# Proppeler_Clock.net
KiCad netlist of a schematic drawn in EAGLE
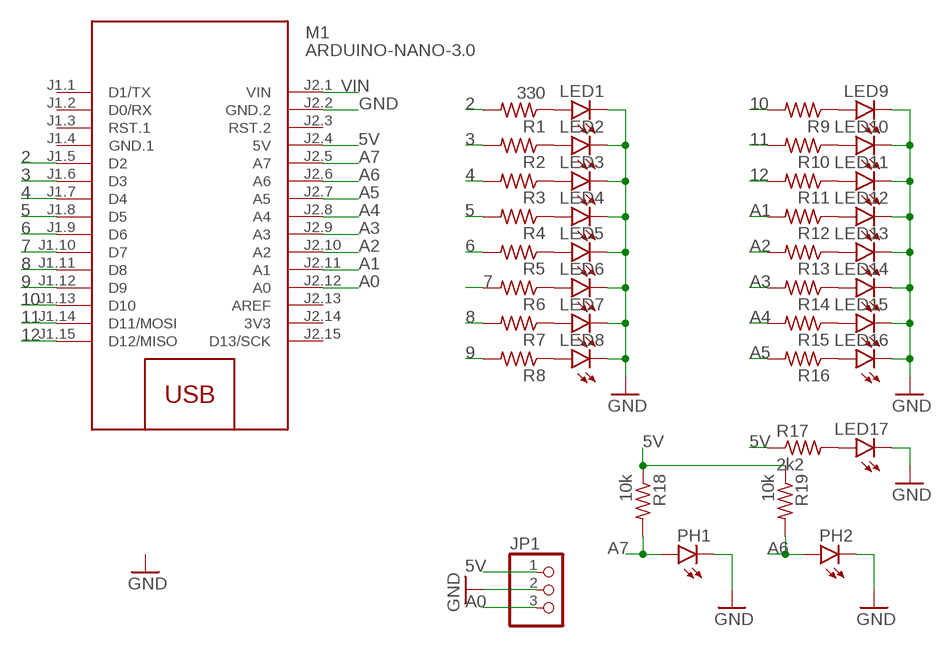
[diagram p0: schematic, sheet 1]

(export (version "E")
  (design (tool "Eeschema 10.0.6"))
  (components
    (comp (ref "JP1")
      (value "PINHD-1X3")
      (footprint "eagle-import:1X03")
      (libsource (lib "eagle-import") (part "PINHD-1X3"))
    )
    (comp (ref "LED1")
      (value "LED3MM")
      (footprint "eagle-import:LED3MM")
      (libsource (lib "eagle-import") (part "LED3MM"))
    )
    (comp (ref "LED2")
      (value "LED3MM")
      (footprint "eagle-import:LED3MM")
      (libsource (lib "eagle-import") (part "LED3MM"))
    )
    (comp (ref "LED3")
      (value "LED3MM")
      (footprint "eagle-import:LED3MM")
      (libsource (lib "eagle-import") (part "LED3MM"))
    )
    (comp (ref "LED4")
      (value "LED3MM")
      (footprint "eagle-import:LED3MM")
      (libsource (lib "eagle-import") (part "LED3MM"))
    )
    (comp (ref "LED5")
      (value "LED3MM")
      (footprint "eagle-import:LED3MM")
      (libsource (lib "eagle-import") (part "LED3MM"))
    )
    (comp (ref "LED6")
      (value "LED3MM")
      (footprint "eagle-import:LED3MM")
      (libsource (lib "eagle-import") (part "LED3MM"))
    )
    (comp (ref "LED7")
      (value "LED3MM")
      (footprint "eagle-import:LED3MM")
      (libsource (lib "eagle-import") (part "LED3MM"))
    )
    (comp (ref "LED8")
      (value "LED3MM")
      (footprint "eagle-import:LED3MM")
      (libsource (lib "eagle-import") (part "LED3MM"))
    )
    (comp (ref "LED9")
      (value "LED3MM")
      (footprint "eagle-import:LED3MM")
      (libsource (lib "eagle-import") (part "LED3MM"))
    )
    (comp (ref "LED10")
      (value "LED3MM")
      (footprint "eagle-import:LED3MM")
      (libsource (lib "eagle-import") (part "LED3MM"))
    )
    (comp (ref "LED11")
      (value "LED3MM")
      (footprint "eagle-import:LED3MM")
      (libsource (lib "eagle-import") (part "LED3MM"))
    )
    (comp (ref "LED12")
      (value "LED3MM")
      (footprint "eagle-import:LED3MM")
      (libsource (lib "eagle-import") (part "LED3MM"))
    )
    (comp (ref "LED13")
      (value "LED3MM")
      (footprint "eagle-import:LED3MM")
      (libsource (lib "eagle-import") (part "LED3MM"))
    )
    (comp (ref "LED14")
      (value "LED3MM")
      (footprint "eagle-import:LED3MM")
      (libsource (lib "eagle-import") (part "LED3MM"))
    )
    (comp (ref "LED15")
      (value "LED3MM")
      (footprint "eagle-import:LED3MM")
      (libsource (lib "eagle-import") (part "LED3MM"))
    )
    (comp (ref "LED16")
      (value "LED3MM")
      (footprint "eagle-import:LED3MM")
      (libsource (lib "eagle-import") (part "LED3MM"))
    )
    (comp (ref "LED17")
      (value "LED3MM")
      (footprint "eagle-import:LED3MM")
      (libsource (lib "eagle-import") (part "LED3MM"))
    )
    (comp (ref "M1")
      (value "ARDUINO-NANO-3.0")
      (footprint "eagle-import:ARDUINO-NANO-3.0")
      (libsource (lib "eagle-import") (part "ARDUINO-NANO-3.0"))
    )
    (comp (ref "PH1")
      (value "LED3MM")
      (footprint "eagle-import:LED3MM")
      (libsource (lib "eagle-import") (part "LED3MM"))
    )
    (comp (ref "PH2")
      (value "LED3MM")
      (footprint "eagle-import:LED3MM")
      (libsource (lib "eagle-import") (part "LED3MM"))
    )
    (comp (ref "R1")
      (value "330")
      (footprint "eagle-import:0204_7")
      (libsource (lib "eagle-import") (part "R-US_0204/7"))
    )
    (comp (ref "R2")
      (value "R-US_0204/7")
      (footprint "eagle-import:0204_7")
      (libsource (lib "eagle-import") (part "R-US_0204/7"))
    )
    (comp (ref "R3")
      (value "R-US_0204/7")
      (footprint "eagle-import:0204_7")
      (libsource (lib "eagle-import") (part "R-US_0204/7"))
    )
    (comp (ref "R4")
      (value "R-US_0204/7")
      (footprint "eagle-import:0204_7")
      (libsource (lib "eagle-import") (part "R-US_0204/7"))
    )
    (comp (ref "R5")
      (value "R-US_0204/7")
      (footprint "eagle-import:0204_7")
      (libsource (lib "eagle-import") (part "R-US_0204/7"))
    )
    (comp (ref "R6")
      (value "R-US_0204/7")
      (footprint "eagle-import:0204_7")
      (libsource (lib "eagle-import") (part "R-US_0204/7"))
    )
    (comp (ref "R7")
      (value "R-US_0204/7")
      (footprint "eagle-import:0204_7")
      (libsource (lib "eagle-import") (part "R-US_0204/7"))
    )
    (comp (ref "R8")
      (value "R-US_0204/7")
      (footprint "eagle-import:0204_7")
      (libsource (lib "eagle-import") (part "R-US_0204/7"))
    )
    (comp (ref "R9")
      (value "R-US_0204/7")
      (footprint "eagle-import:0204_7")
      (libsource (lib "eagle-import") (part "R-US_0204/7"))
    )
    (comp (ref "R10")
      (value "R-US_0204/7")
      (footprint "eagle-import:0204_7")
      (libsource (lib "eagle-import") (part "R-US_0204/7"))
    )
    (comp (ref "R11")
      (value "R-US_0204/7")
      (footprint "eagle-import:0204_7")
      (libsource (lib "eagle-import") (part "R-US_0204/7"))
    )
    (comp (ref "R12")
      (value "R-US_0204/7")
      (footprint "eagle-import:0204_7")
      (libsource (lib "eagle-import") (part "R-US_0204/7"))
    )
    (comp (ref "R13")
      (value "R-US_0204/7")
      (footprint "eagle-import:0204_7")
      (libsource (lib "eagle-import") (part "R-US_0204/7"))
    )
    (comp (ref "R14")
      (value "R-US_0204/7")
      (footprint "eagle-import:0204_7")
      (libsource (lib "eagle-import") (part "R-US_0204/7"))
    )
    (comp (ref "R15")
      (value "R-US_0204/7")
      (footprint "eagle-import:0204_7")
      (libsource (lib "eagle-import") (part "R-US_0204/7"))
    )
    (comp (ref "R16")
      (value "R-US_0204/7")
      (footprint "eagle-import:0204_7")
      (libsource (lib "eagle-import") (part "R-US_0204/7"))
    )
    (comp (ref "R17")
      (value "2k2")
      (footprint "eagle-import:0204_7")
      (libsource (lib "eagle-import") (part "R-US_0204/7"))
    )
    (comp (ref "R18")
      (value "10k")
      (footprint "eagle-import:0204_7")
      (libsource (lib "eagle-import") (part "R-US_0204/7"))
    )
    (comp (ref "R19")
      (value "10k")
      (footprint "eagle-import:0204_7")
      (libsource (lib "eagle-import") (part "R-US_0204/7"))
    )
  )
  (nets
    (net (code "1") (name "/2") (class "Default")
      (node (ref "M1") (pin "J1.5") (pinfunction "D2_J1.5") (pintype "bidirectional"))
      (node (ref "R1") (pin "2") (pinfunction "2_2") (pintype "passive"))
    )
    (net (code "2") (name "/3") (class "Default")
      (node (ref "M1") (pin "J1.6") (pinfunction "D3_J1.6") (pintype "bidirectional"))
      (node (ref "R2") (pin "2") (pinfunction "2_2") (pintype "passive"))
    )
    (net (code "3") (name "/3V3") (class "Default")
      (node (ref "M1") (pin "J2.14") (pinfunction "3V3_J2.14") (pintype "power_in"))
    )
    (net (code "4") (name "/4") (class "Default")
      (node (ref "M1") (pin "J1.7") (pinfunction "D4_J1.7") (pintype "bidirectional"))
      (node (ref "R3") (pin "2") (pinfunction "2_2") (pintype "passive"))
    )
    (net (code "5") (name "/5") (class "Default")
      (node (ref "M1") (pin "J1.8") (pinfunction "D5_J1.8") (pintype "bidirectional"))
      (node (ref "R4") (pin "2") (pinfunction "2_2") (pintype "passive"))
    )
    (net (code "6") (name "/5V") (class "Default")
      (node (ref "JP1") (pin "1") (pinfunction "1_1") (pintype "passive"))
      (node (ref "M1") (pin "J2.4") (pinfunction "5V_J2.4") (pintype "power_in"))
      (node (ref "R17") (pin "1") (pinfunction "1_1") (pintype "passive"))
      (node (ref "R18") (pin "1") (pinfunction "1_1") (pintype "passive"))
      (node (ref "R19") (pin "1") (pinfunction "1_1") (pintype "passive"))
    )
    (net (code "7") (name "/6") (class "Default")
      (node (ref "M1") (pin "J1.9") (pinfunction "D6_J1.9") (pintype "bidirectional"))
      (node (ref "R5") (pin "2") (pinfunction "2_2") (pintype "passive"))
    )
    (net (code "8") (name "/7") (class "Default")
      (node (ref "M1") (pin "J1.10") (pinfunction "D7_J1.10") (pintype "bidirectional"))
      (node (ref "R6") (pin "2") (pinfunction "2_2") (pintype "passive"))
    )
    (net (code "9") (name "/8") (class "Default")
      (node (ref "M1") (pin "J1.11") (pinfunction "D8_J1.11") (pintype "bidirectional"))
      (node (ref "R7") (pin "2") (pinfunction "2_2") (pintype "passive"))
    )
    (net (code "10") (name "/9") (class "Default")
      (node (ref "M1") (pin "J1.12") (pinfunction "D9_J1.12") (pintype "bidirectional"))
      (node (ref "R8") (pin "2") (pinfunction "2_2") (pintype "passive"))
    )
    (net (code "11") (name "/10") (class "Default")
      (node (ref "M1") (pin "J1.13") (pinfunction "D10_J1.13") (pintype "bidirectional"))
      (node (ref "R9") (pin "2") (pinfunction "2_2") (pintype "passive"))
    )
    (net (code "12") (name "/11") (class "Default")
      (node (ref "M1") (pin "J1.14") (pinfunction "D11/MOSI_J1.14") (pintype "bidirectional"))
      (node (ref "R10") (pin "2") (pinfunction "2_2") (pintype "passive"))
    )
    (net (code "13") (name "/12") (class "Default")
      (node (ref "M1") (pin "J1.15") (pinfunction "D12/MISO_J1.15") (pintype "bidirectional"))
      (node (ref "R11") (pin "2") (pinfunction "2_2") (pintype "passive"))
    )
    (net (code "14") (name "/A0") (class "Default")
      (node (ref "JP1") (pin "3") (pinfunction "3_3") (pintype "passive"))
      (node (ref "M1") (pin "J2.12") (pinfunction "A0_J2.12") (pintype "bidirectional"))
    )
    (net (code "15") (name "/A1") (class "Default")
      (node (ref "M1") (pin "J2.11") (pinfunction "A1_J2.11") (pintype "bidirectional"))
      (node (ref "R12") (pin "2") (pinfunction "2_2") (pintype "passive"))
    )
    (net (code "16") (name "/A2") (class "Default")
      (node (ref "M1") (pin "J2.10") (pinfunction "A2_J2.10") (pintype "bidirectional"))
      (node (ref "R13") (pin "2") (pinfunction "2_2") (pintype "passive"))
    )
    (net (code "17") (name "/A3") (class "Default")
      (node (ref "M1") (pin "J2.9") (pinfunction "A3_J2.9") (pintype "bidirectional"))
      (node (ref "R14") (pin "2") (pinfunction "2_2") (pintype "passive"))
    )
    (net (code "18") (name "/A4") (class "Default")
      (node (ref "M1") (pin "J2.8") (pinfunction "A4_J2.8") (pintype "bidirectional"))
      (node (ref "R15") (pin "2") (pinfunction "2_2") (pintype "passive"))
    )
    (net (code "19") (name "/A5") (class "Default")
      (node (ref "M1") (pin "J2.7") (pinfunction "A5_J2.7") (pintype "bidirectional"))
      (node (ref "R16") (pin "2") (pinfunction "2_2") (pintype "passive"))
    )
    (net (code "20") (name "/A6") (class "Default")
      (node (ref "M1") (pin "J2.6") (pinfunction "A6_J2.6") (pintype "bidirectional"))
      (node (ref "PH2") (pin "A") (pinfunction "A_A") (pintype "passive"))
      (node (ref "R19") (pin "2") (pinfunction "2_2") (pintype "passive"))
    )
    (net (code "21") (name "/A7") (class "Default")
      (node (ref "M1") (pin "J2.5") (pinfunction "A7_J2.5") (pintype "bidirectional"))
      (node (ref "PH1") (pin "A") (pinfunction "A_A") (pintype "passive"))
      (node (ref "R18") (pin "2") (pinfunction "2_2") (pintype "passive"))
    )
    (net (code "22") (name "/GND.1") (class "Default")
      (node (ref "M1") (pin "J1.4") (pinfunction "GND.1_J1.4") (pintype "power_in"))
    )
    (net (code "23") (name "/VIN") (class "Default")
      (node (ref "M1") (pin "J2.1") (pinfunction "VIN_J2.1") (pintype "power_in"))
    )
    (net (code "24") (name "GND") (class "Default")
      (node (ref "JP1") (pin "2") (pinfunction "2_2") (pintype "passive"))
      (node (ref "LED1") (pin "K") (pinfunction "C_K") (pintype "passive"))
      (node (ref "LED10") (pin "K") (pinfunction "C_K") (pintype "passive"))
      (node (ref "LED11") (pin "K") (pinfunction "C_K") (pintype "passive"))
      (node (ref "LED12") (pin "K") (pinfunction "C_K") (pintype "passive"))
      (node (ref "LED13") (pin "K") (pinfunction "C_K") (pintype "passive"))
      (node (ref "LED14") (pin "K") (pinfunction "C_K") (pintype "passive"))
      (node (ref "LED15") (pin "K") (pinfunction "C_K") (pintype "passive"))
      (node (ref "LED16") (pin "K") (pinfunction "C_K") (pintype "passive"))
      (node (ref "LED17") (pin "K") (pinfunction "C_K") (pintype "passive"))
      (node (ref "LED2") (pin "K") (pinfunction "C_K") (pintype "passive"))
      (node (ref "LED3") (pin "K") (pinfunction "C_K") (pintype "passive"))
      (node (ref "LED4") (pin "K") (pinfunction "C_K") (pintype "passive"))
      (node (ref "LED5") (pin "K") (pinfunction "C_K") (pintype "passive"))
      (node (ref "LED6") (pin "K") (pinfunction "C_K") (pintype "passive"))
      (node (ref "LED7") (pin "K") (pinfunction "C_K") (pintype "passive"))
      (node (ref "LED8") (pin "K") (pinfunction "C_K") (pintype "passive"))
      (node (ref "LED9") (pin "K") (pinfunction "C_K") (pintype "passive"))
      (node (ref "M1") (pin "J2.2") (pinfunction "GND.2_J2.2") (pintype "power_in"))
      (node (ref "PH1") (pin "K") (pinfunction "C_K") (pintype "passive"))
      (node (ref "PH2") (pin "K") (pinfunction "C_K") (pintype "passive"))
    )
    (net (code "25") (name "Net-(LED1-PadA)") (class "Default")
      (node (ref "LED1") (pin "A") (pinfunction "A_A") (pintype "passive"))
      (node (ref "R1") (pin "1") (pinfunction "1_1") (pintype "passive"))
    )
    (net (code "26") (name "Net-(LED2-PadA)") (class "Default")
      (node (ref "LED2") (pin "A") (pinfunction "A_A") (pintype "passive"))
      (node (ref "R2") (pin "1") (pinfunction "1_1") (pintype "passive"))
    )
    (net (code "27") (name "Net-(LED3-PadA)") (class "Default")
      (node (ref "LED3") (pin "A") (pinfunction "A_A") (pintype "passive"))
      (node (ref "R3") (pin "1") (pinfunction "1_1") (pintype "passive"))
    )
    (net (code "28") (name "Net-(LED4-PadA)") (class "Default")
      (node (ref "LED4") (pin "A") (pinfunction "A_A") (pintype "passive"))
      (node (ref "R4") (pin "1") (pinfunction "1_1") (pintype "passive"))
    )
    (net (code "29") (name "Net-(LED5-PadA)") (class "Default")
      (node (ref "LED5") (pin "A") (pinfunction "A_A") (pintype "passive"))
      (node (ref "R5") (pin "1") (pinfunction "1_1") (pintype "passive"))
    )
    (net (code "30") (name "Net-(LED6-PadA)") (class "Default")
      (node (ref "LED6") (pin "A") (pinfunction "A_A") (pintype "passive"))
      (node (ref "R6") (pin "1") (pinfunction "1_1") (pintype "passive"))
    )
    (net (code "31") (name "Net-(LED7-PadA)") (class "Default")
      (node (ref "LED7") (pin "A") (pinfunction "A_A") (pintype "passive"))
      (node (ref "R7") (pin "1") (pinfunction "1_1") (pintype "passive"))
    )
    (net (code "32") (name "Net-(LED8-PadA)") (class "Default")
      (node (ref "LED8") (pin "A") (pinfunction "A_A") (pintype "passive"))
      (node (ref "R8") (pin "1") (pinfunction "1_1") (pintype "passive"))
    )
    (net (code "33") (name "Net-(LED9-PadA)") (class "Default")
      (node (ref "LED9") (pin "A") (pinfunction "A_A") (pintype "passive"))
      (node (ref "R9") (pin "1") (pinfunction "1_1") (pintype "passive"))
    )
    (net (code "34") (name "Net-(LED10-PadA)") (class "Default")
      (node (ref "LED10") (pin "A") (pinfunction "A_A") (pintype "passive"))
      (node (ref "R10") (pin "1") (pinfunction "1_1") (pintype "passive"))
    )
    (net (code "35") (name "Net-(LED11-PadA)") (class "Default")
      (node (ref "LED11") (pin "A") (pinfunction "A_A") (pintype "passive"))
      (node (ref "R11") (pin "1") (pinfunction "1_1") (pintype "passive"))
    )
    (net (code "36") (name "Net-(LED12-PadA)") (class "Default")
      (node (ref "LED12") (pin "A") (pinfunction "A_A") (pintype "passive"))
      (node (ref "R12") (pin "1") (pinfunction "1_1") (pintype "passive"))
    )
    (net (code "37") (name "Net-(LED13-PadA)") (class "Default")
      (node (ref "LED13") (pin "A") (pinfunction "A_A") (pintype "passive"))
      (node (ref "R13") (pin "1") (pinfunction "1_1") (pintype "passive"))
    )
    (net (code "38") (name "Net-(LED14-PadA)") (class "Default")
      (node (ref "LED14") (pin "A") (pinfunction "A_A") (pintype "passive"))
      (node (ref "R14") (pin "1") (pinfunction "1_1") (pintype "passive"))
    )
    (net (code "39") (name "Net-(LED15-PadA)") (class "Default")
      (node (ref "LED15") (pin "A") (pinfunction "A_A") (pintype "passive"))
      (node (ref "R15") (pin "1") (pinfunction "1_1") (pintype "passive"))
    )
    (net (code "40") (name "Net-(LED16-PadA)") (class "Default")
      (node (ref "LED16") (pin "A") (pinfunction "A_A") (pintype "passive"))
      (node (ref "R16") (pin "1") (pinfunction "1_1") (pintype "passive"))
    )
    (net (code "41") (name "Net-(LED17-PadA)") (class "Default")
      (node (ref "LED17") (pin "A") (pinfunction "A_A") (pintype "passive"))
      (node (ref "R17") (pin "2") (pinfunction "2_2") (pintype "passive"))
    )
    (net (code "42") (name "unconnected-(M1-AREF-PadJ2.13)") (class "Default")
      (node (ref "M1") (pin "J2.13") (pinfunction "AREF_J2.13") (pintype "bidirectional"))
    )
    (net (code "43") (name "unconnected-(M1-D0{slash}RX-PadJ1.2)") (class "Default")
      (node (ref "M1") (pin "J1.2") (pinfunction "D0/RX_J1.2") (pintype "bidirectional"))
    )
    (net (code "44") (name "unconnected-(M1-D1{slash}TX-PadJ1.1)") (class "Default")
      (node (ref "M1") (pin "J1.1") (pinfunction "D1/TX_J1.1") (pintype "bidirectional"))
    )
    (net (code "45") (name "unconnected-(M1-D13{slash}SCK-PadJ2.15)") (class "Default")
      (node (ref "M1") (pin "J2.15") (pinfunction "D13/SCK_J2.15") (pintype "bidirectional"))
    )
    (net (code "46") (name "unconnected-(M1-RST.1-PadJ1.3)") (class "Default")
      (node (ref "M1") (pin "J1.3") (pinfunction "RST.1_J1.3") (pintype "bidirectional"))
    )
    (net (code "47") (name "unconnected-(M1-RST.2-PadJ2.3)") (class "Default")
      (node (ref "M1") (pin "J2.3") (pinfunction "RST.2_J2.3") (pintype "bidirectional"))
    )
  )
)
